# JacdacKeyboardKey_46.net
KiCad netlist of a schematic drawn in Altium Designer
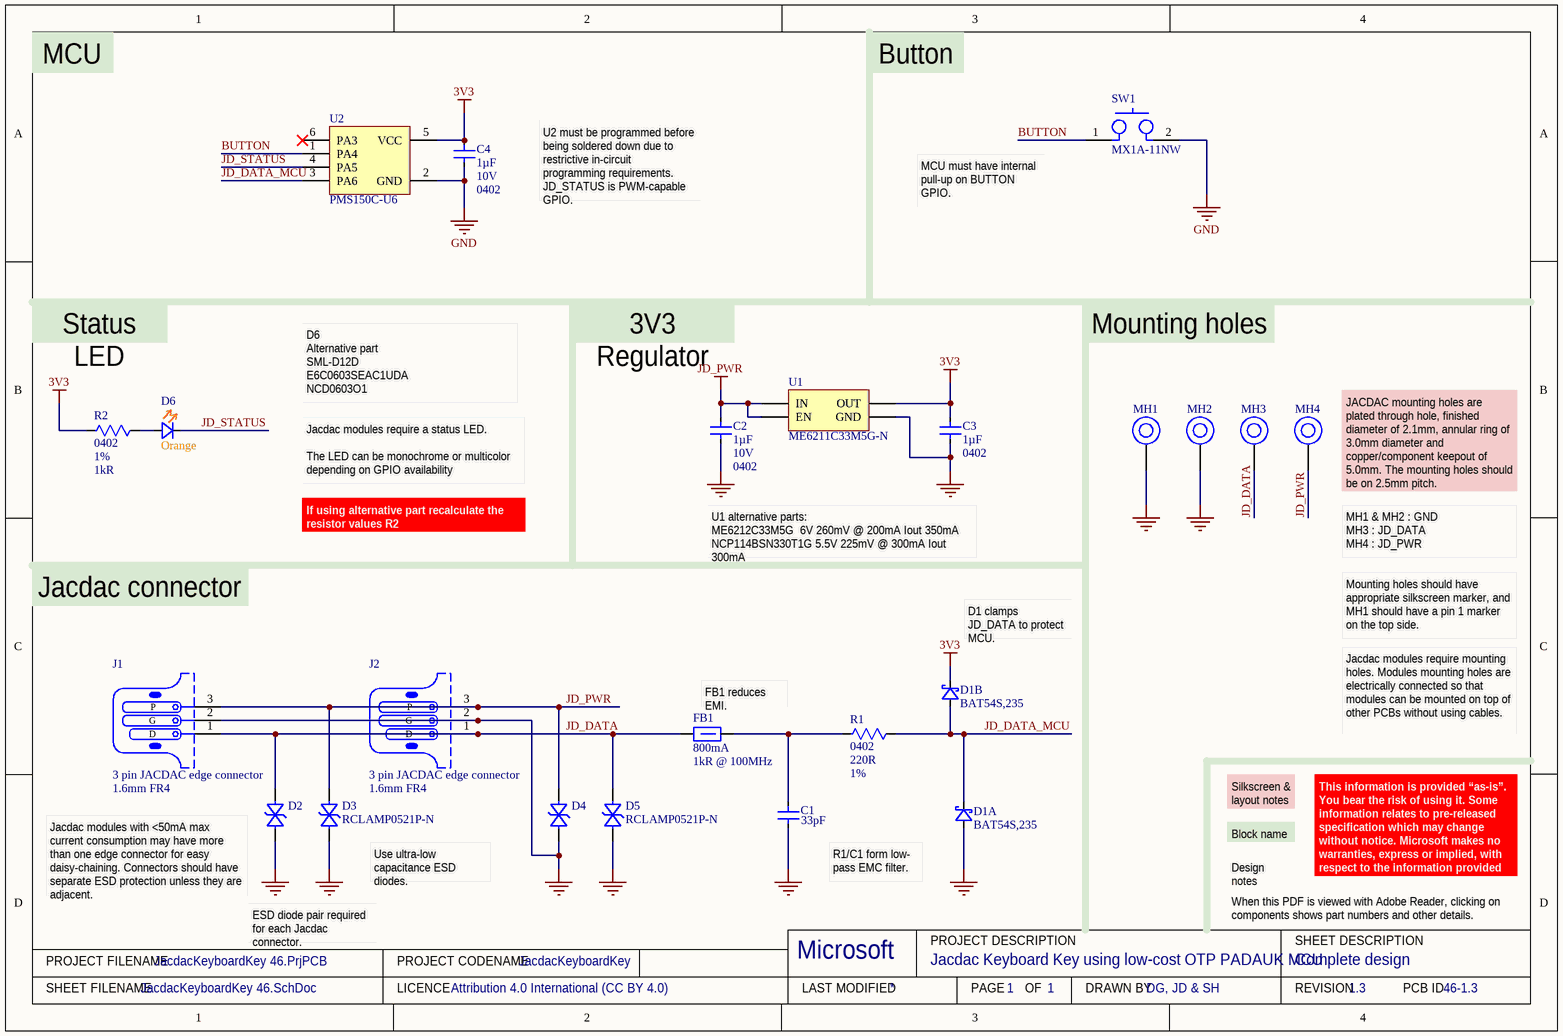
[diagram p0: JacdacKeyboardKey 46.SchDoc]

(export (version "E")
  (design (tool "Eeschema 10.0.6"))
  (components
    (comp (ref "C1")
      (value "CL05C330JB5NNNC")
      (footprint "C0402_0.55MM - without outline")
      (description "CAP CER 33PF 50V C0G/NP0 0402")
      (fields
        (field (name "MANUFACTURER") "Samsung")
        (field (name "TOLERANCE") "5%")
        (field (name "CAPACITANCE") "33pF")
      )
      (libsource (lib "Samsung") (part "CL05C330JB5NNNC"))
    )
    (comp (ref "C2")
      (value "CL05A105KP5NNNC")
      (footprint "C0402_0.55MM - without outline")
      (description "CAP CER 1UF 10V X5R 0402")
      (fields
        (field (name "MANUFACTURER") "Samsung")
        (field (name "TOLERANCE") "10%")
        (field (name "CAPACITANCE") "1µF")
        (field (name "VOLTAGE RATING") "10V")
        (field (name "CASE CODE (IMPERIAL)") "0402")
        (field (name "CREATED") "DG")
        (field (name "CHECKED") "?")
      )
      (libsource (lib "Samsung") (part "CL05A105KP5NNNC"))
    )
    (comp (ref "C3")
      (value "CL05A105KP5NNNC")
      (footprint "C0402_0.55MM - without outline")
      (description "CAP CER 1UF 10V X5R 0402")
      (fields
        (field (name "MANUFACTURER") "Samsung")
        (field (name "TOLERANCE") "10%")
        (field (name "CAPACITANCE") "1µF")
        (field (name "CASE CODE (IMPERIAL)") "0402")
        (field (name "CREATED") "DG")
        (field (name "CHECKED") "?")
      )
      (libsource (lib "Samsung") (part "CL05A105KP5NNNC"))
    )
    (comp (ref "C4")
      (value "CL05A105KP5NNNC")
      (footprint "C0402_0.55MM - without outline")
      (description "CAP CER 1UF 10V X5R 0402")
      (fields
        (field (name "MANUFACTURER") "Samsung")
        (field (name "TOLERANCE") "10%")
        (field (name "CAPACITANCE") "1µF")
        (field (name "VOLTAGE RATING") "10V")
        (field (name "CASE CODE (IMPERIAL)") "0402")
        (field (name "CREATED") "DG")
        (field (name "CHECKED") "?")
      )
      (libsource (lib "Samsung") (part "CL05A105KP5NNNC"))
    )
    (comp (ref "D1")
      (value "BAT54S")
      (footprint "NXP-BAT54S-TO-236AB - without outline")
      (description "DIODE ARRAY SCHOTTKY 30V SOT23")
      (fields (field (name "MANUFACTURER") "Nexperia") (field (name "MANUFACTURER PART NUMBER") "BAT54S,235"))
      (libsource (lib "NXP") (part "BAT54S"))
    )
    (comp (ref "D2")
      (value "RCLAMP0521P-N")
      (footprint "TVS 0402 - L")
      (description "Bidirectional 5V (Max) 6V 16V 3.5A (8/20us) 0402 TVS RoHS")
      (fields
        (field (name "MANUFACTURER") "Born Semiconductor")
        (field (name "CREATED BY") "D Gakure")
        (field (name "CHECKED BY") "?")
      )
      (libsource (lib "BornSemiconductor") (part "RCLAMP0521P-N"))
    )
    (comp (ref "D3")
      (value "RCLAMP0521P-N")
      (footprint "TVS 0402 - L")
      (description "Bidirectional 5V (Max) 6V 16V 3.5A (8/20us) 0402 TVS RoHS")
      (fields
        (field (name "MANUFACTURER") "Born Semiconductor")
        (field (name "MANUFACTURER PART NUMBER") "RCLAMP0521P-N")
        (field (name "CREATED BY") "D Gakure")
        (field (name "CHECKED BY") "?")
      )
      (libsource (lib "BornSemiconductor") (part "RCLAMP0521P-N"))
    )
    (comp (ref "D4")
      (value "RCLAMP0521P-N")
      (footprint "TVS 0402 - L")
      (description "Bidirectional 5V (Max) 6V 16V 3.5A (8/20us) 0402 TVS RoHS")
      (fields
        (field (name "MANUFACTURER") "Born Semiconductor")
        (field (name "CREATED BY") "D Gakure")
        (field (name "CHECKED BY") "?")
      )
      (libsource (lib "BornSemiconductor") (part "RCLAMP0521P-N"))
    )
    (comp (ref "D5")
      (value "RCLAMP0521P-N")
      (footprint "TVS 0402 - L")
      (description "Bidirectional 5V (Max) 6V 16V 3.5A (8/20us) 0402 TVS RoHS")
      (fields
        (field (name "MANUFACTURER") "Born Semiconductor")
        (field (name "MANUFACTURER PART NUMBER") "RCLAMP0521P-N")
        (field (name "CREATED BY") "D Gakure")
        (field (name "CHECKED BY") "?")
      )
      (libsource (lib "BornSemiconductor") (part "RCLAMP0521P-N"))
    )
    (comp (ref "D6")
      (value "~")
      (footprint "0603 Orange")
      (description "LED ORANGE DIFFUSED 0603 SMD")
      (fields
        (field (name "MANUFACTURER") "Everlight Elec")
        (field (name "MANUFACTURER PART NUMBER") "19-217/S2C-AQ1R1B/3T")
        (field (name "COLOUR") "Orange")
      )
      (libsource (lib "EverlightElec") (part "19-217/S2C-AQ1R1B/3T"))
    )
    (comp (ref "FB1")
      (value "TDK MPZ1608S102ATA00")
      (footprint "TDK MPZ1608 0.8mm - without outline")
      (description "0603 1k@100MHz 0.8A chip")
      (fields
        (field (name "TOLERANCE") "25%")
        (field (name "MANUFACTURER") "TDK")
        (field (name "CURRENT RATING") "800mA")
        (field (name "IMPEDANCE") "1kR @ 100MHz")
      )
      (libsource (lib "TDK") (part "TDK MPZ1608S102ATA00"))
    )
    (comp (ref "J1")
      (value "3 pin JACDAC edge connector")
      (footprint "JACDAC_EDGE_CONNECTOR_NO_TRACES")
      (description "3 pin Jacdac edge connector 1.27mm pitch")
      (fields
        (field (name "MANUFACTURER PART NUMBER") "JACDAC_EDGE_CONNECTOR")
        (field (name "PCB TYPE") "1.6mm FR4")
        (field (name "CHECKED BY") "?")
        (field (name "CREATED BY") "D. Gakure")
      )
      (libsource (lib "generic-con") (part "Jacdac edge connector"))
    )
    (comp (ref "J2")
      (value "3 pin JACDAC edge connector")
      (footprint "JACDAC_EDGE_CONNECTOR_NO_TRACES")
      (description "3 pin Jacdac edge connector 1.27mm pitch")
      (fields
        (field (name "MANUFACTURER PART NUMBER") "JACDAC_EDGE_CONNECTOR")
        (field (name "PCB TYPE") "1.6mm FR4")
        (field (name "CHECKED BY") "?")
        (field (name "CREATED BY") "D. Gakure")
      )
      (libsource (lib "generic-con") (part "Jacdac edge connector"))
    )
    (comp (ref "MH1")
      (value "MH_5.0MMK_3.0MMC_2.1MMD_PTH")
      (footprint "MH_5.0MMK_3.0MMC_2.1MMD_PTH")
      (description "Mounting Hole 5.0mm keepout, 3.0mm annualar ring and 2.1mm Drill PTH")
      (libsource (lib "generic") (part "MH_5.0MMK_3.0MMC_2.1MMD_PTH"))
    )
    (comp (ref "MH2")
      (value "MH_5.0MMK_3.0MMC_2.1MMD_PTH")
      (footprint "MH_5.0MMK_3.0MMC_2.1MMD_PTH")
      (description "Mounting Hole 5.0mm keepout, 3.0mm annualar ring and 2.1mm Drill PTH")
      (libsource (lib "generic") (part "MH_5.0MMK_3.0MMC_2.1MMD_PTH"))
    )
    (comp (ref "MH3")
      (value "MH_5.0MMK_3.0MMC_2.1MMD_PTH")
      (footprint "MH_5.0MMK_3.0MMC_2.1MMD_PTH")
      (description "Mounting Hole 5.0mm keepout, 3.0mm annualar ring and 2.1mm Drill PTH")
      (libsource (lib "generic") (part "MH_5.0MMK_3.0MMC_2.1MMD_PTH"))
    )
    (comp (ref "MH4")
      (value "MH_5.0MMK_3.0MMC_2.1MMD_PTH")
      (footprint "MH_5.0MMK_3.0MMC_2.1MMD_PTH")
      (description "Mounting Hole 5.0mm keepout, 3.0mm annualar ring and 2.1mm Drill PTH")
      (libsource (lib "generic") (part "MH_5.0MMK_3.0MMC_2.1MMD_PTH"))
    )
    (comp (ref "R1")
      (value "RC0402FR-07220RL")
      (footprint "R0402 - Without outline")
      (description "RES SMD 220 OHM 1% 1/16W 0402")
      (fields
        (field (name "MANUFACTURER") "Yageo")
        (field (name "CASE CODE (IMPERIAL)") "0402")
        (field (name "RESISTANCE") "220R")
        (field (name "TOLERANCE") "1%")
        (field (name "CREATED") "D.G")
        (field (name "CHECKED") "?")
      )
      (libsource (lib "Yageo") (part "RC0402FR-07220RL"))
    )
    (comp (ref "R2")
      (value "RC0402FR-071KL")
      (footprint "R0402 - Without outline")
      (description "RES SMD 1K OHM 1% 1/16W 0402")
      (fields
        (field (name "MANUFACTURER") "Yageo")
        (field (name "CASE CODE (IMPERIAL)") "0402")
        (field (name "TOLERANCE") "1%")
        (field (name "RESISTANCE") "1kR")
        (field (name "CREATED") "D.G")
        (field (name "CHECKED") "?")
      )
      (libsource (lib "Yageo") (part "RC0402FR-071KL"))
    )
    (comp (ref "SW1")
      (value "Mechanical keyboard mount")
      (footprint "MX1A-11NW:MX1A-11NW")
      (description "Pushbutton Switch SPST-NO Keyswitch Through Hole")
      (fields (field (name "MANUFACTURER PART NUMBER 1") "MX1A-11NW"))
      (libsource (lib "Cherry") (part "MX1A-11NW"))
    )
    (comp (ref "U1")
      (value "ME6211C33M5G-N")
      (footprint "MICRONE-SOT23-5")
      (description "6V 260mV @ 200mA(typ) - - Fixed 3.3V SOT-23-5 Linear Voltage Regulators (LDO) ROHS")
      (fields
        (field (name "MANUFACTURER") "MICRONE(Nanjing Micro One Elec)")
        (field (name "MANUFACTURER PART NUMBER") "ME6211C33M5G-N")
        (field (name "CREATED") "DG")
        (field (name "CHECKED") "?")
      )
      (libsource (lib "MICRONE(NanjingMicroOneElec)") (part "ME6211C33M5G-N"))
    )
    (comp (ref "U2")
      (value "PMS150C")
      (footprint "PADAUK-SOT23-6:SOT23-6")
      (description "8bit OTP Type IO Controller")
      (fields (field (name "MANUFACTURER PART NUMBER") "PMS150C-U6") (field (name "MANUFACTURER") "PADAUK"))
      (libsource (lib "PADAUK") (part "PMS150C"))
    )
  )
  (nets
    (net (code "1") (name "/BUTTON") (class "Default")
      (node (ref "SW1") (pin "1") (pinfunction "A_1") (pintype "passive"))
      (node (ref "U2") (pin "1") (pinfunction "PA4_1") (pintype "passive"))
    )
    (net (code "2") (name "/JD_DATA") (class "Default")
      (node (ref "D2") (pin "1") (pinfunction "K_1") (pintype "passive"))
      (node (ref "D5") (pin "1") (pinfunction "K_1") (pintype "passive"))
      (node (ref "FB1") (pin "1") (pinfunction "1_1") (pintype "passive"))
      (node (ref "J1") (pin "1") (pinfunction "D_1") (pintype "passive"))
      (node (ref "J2") (pin "1") (pinfunction "D_1") (pintype "passive"))
      (node (ref "MH3") (pin "1") (pinfunction "1_1") (pintype "passive"))
    )
    (net (code "3") (name "/JD_DATA_MCU") (class "Default")
      (node (ref "D1") (pin "3") (pinfunction "A_3") (pintype "passive"))
      (node (ref "R1") (pin "1") (pinfunction "1_1") (pintype "passive"))
      (node (ref "U2") (pin "3") (pinfunction "PA6_3") (pintype "passive"))
    )
    (net (code "4") (name "/JD_STATUS") (class "Default")
      (node (ref "D6") (pin "1") (pinfunction "K_1") (pintype "passive"))
      (node (ref "U2") (pin "4") (pinfunction "PA5_4") (pintype "passive"))
    )
    (net (code "5") (name "3V3") (class "Default")
      (node (ref "C3") (pin "2") (pinfunction "2_2") (pintype "passive"))
      (node (ref "C4") (pin "2") (pinfunction "2_2") (pintype "passive"))
      (node (ref "D1") (pin "2") (pinfunction "K_2") (pintype "passive"))
      (node (ref "R2") (pin "2") (pinfunction "2_2") (pintype "passive"))
      (node (ref "U1") (pin "5") (pinfunction "OUT_5") (pintype "passive"))
      (node (ref "U2") (pin "5") (pinfunction "VCC_5") (pintype "passive"))
    )
    (net (code "6") (name "GND") (class "Default")
      (node (ref "C1") (pin "1") (pinfunction "1_1") (pintype "passive"))
      (node (ref "C2") (pin "1") (pinfunction "1_1") (pintype "passive"))
      (node (ref "C3") (pin "1") (pinfunction "1_1") (pintype "passive"))
      (node (ref "C4") (pin "1") (pinfunction "1_1") (pintype "passive"))
      (node (ref "D1") (pin "1") (pinfunction "A_1") (pintype "passive"))
      (node (ref "D2") (pin "2") (pinfunction "A_2") (pintype "passive"))
      (node (ref "D3") (pin "2") (pinfunction "A_2") (pintype "passive"))
      (node (ref "D4") (pin "2") (pinfunction "A_2") (pintype "passive"))
      (node (ref "D5") (pin "2") (pinfunction "A_2") (pintype "passive"))
      (node (ref "J1") (pin "2") (pinfunction "G_2") (pintype "passive"))
      (node (ref "J2") (pin "2") (pinfunction "G_2") (pintype "passive"))
      (node (ref "MH1") (pin "1") (pinfunction "1_1") (pintype "passive"))
      (node (ref "MH2") (pin "1") (pinfunction "1_1") (pintype "passive"))
      (node (ref "SW1") (pin "2") (pinfunction "B_2") (pintype "passive"))
      (node (ref "U1") (pin "2") (pinfunction "GND_2") (pintype "passive"))
      (node (ref "U2") (pin "2") (pinfunction "GND_2") (pintype "passive"))
    )
    (net (code "7") (name "JD_PWR") (class "Default")
      (node (ref "C2") (pin "2") (pinfunction "2_2") (pintype "passive"))
      (node (ref "D3") (pin "1") (pinfunction "K_1") (pintype "passive"))
      (node (ref "D4") (pin "1") (pinfunction "K_1") (pintype "passive"))
      (node (ref "J1") (pin "3") (pinfunction "P_3") (pintype "passive"))
      (node (ref "J2") (pin "3") (pinfunction "P_3") (pintype "passive"))
      (node (ref "MH4") (pin "1") (pinfunction "1_1") (pintype "passive"))
      (node (ref "U1") (pin "1") (pinfunction "IN_1") (pintype "passive"))
      (node (ref "U1") (pin "3") (pinfunction "EN_3") (pintype "passive"))
    )
    (net (code "8") (name "Net-(C1-Pad2)") (class "Default")
      (node (ref "C1") (pin "2") (pinfunction "2_2") (pintype "passive"))
      (node (ref "FB1") (pin "2") (pinfunction "2_2") (pintype "passive"))
      (node (ref "R1") (pin "2") (pinfunction "2_2") (pintype "passive"))
    )
    (net (code "9") (name "Net-(D6-A)") (class "Default")
      (node (ref "D6") (pin "2") (pinfunction "A_2") (pintype "passive"))
      (node (ref "R2") (pin "1") (pinfunction "1_1") (pintype "passive"))
    )
    (net (code "10") (name "unconnected-(U2-PA3-Pad6)") (class "Default")
      (node (ref "U2") (pin "6") (pinfunction "PA3_6") (pintype "passive+no_connect"))
    )
  )
)
